# ATTiny85_5LED_VUSB.net
KiCad netlist of a schematic drawn in EAGLE
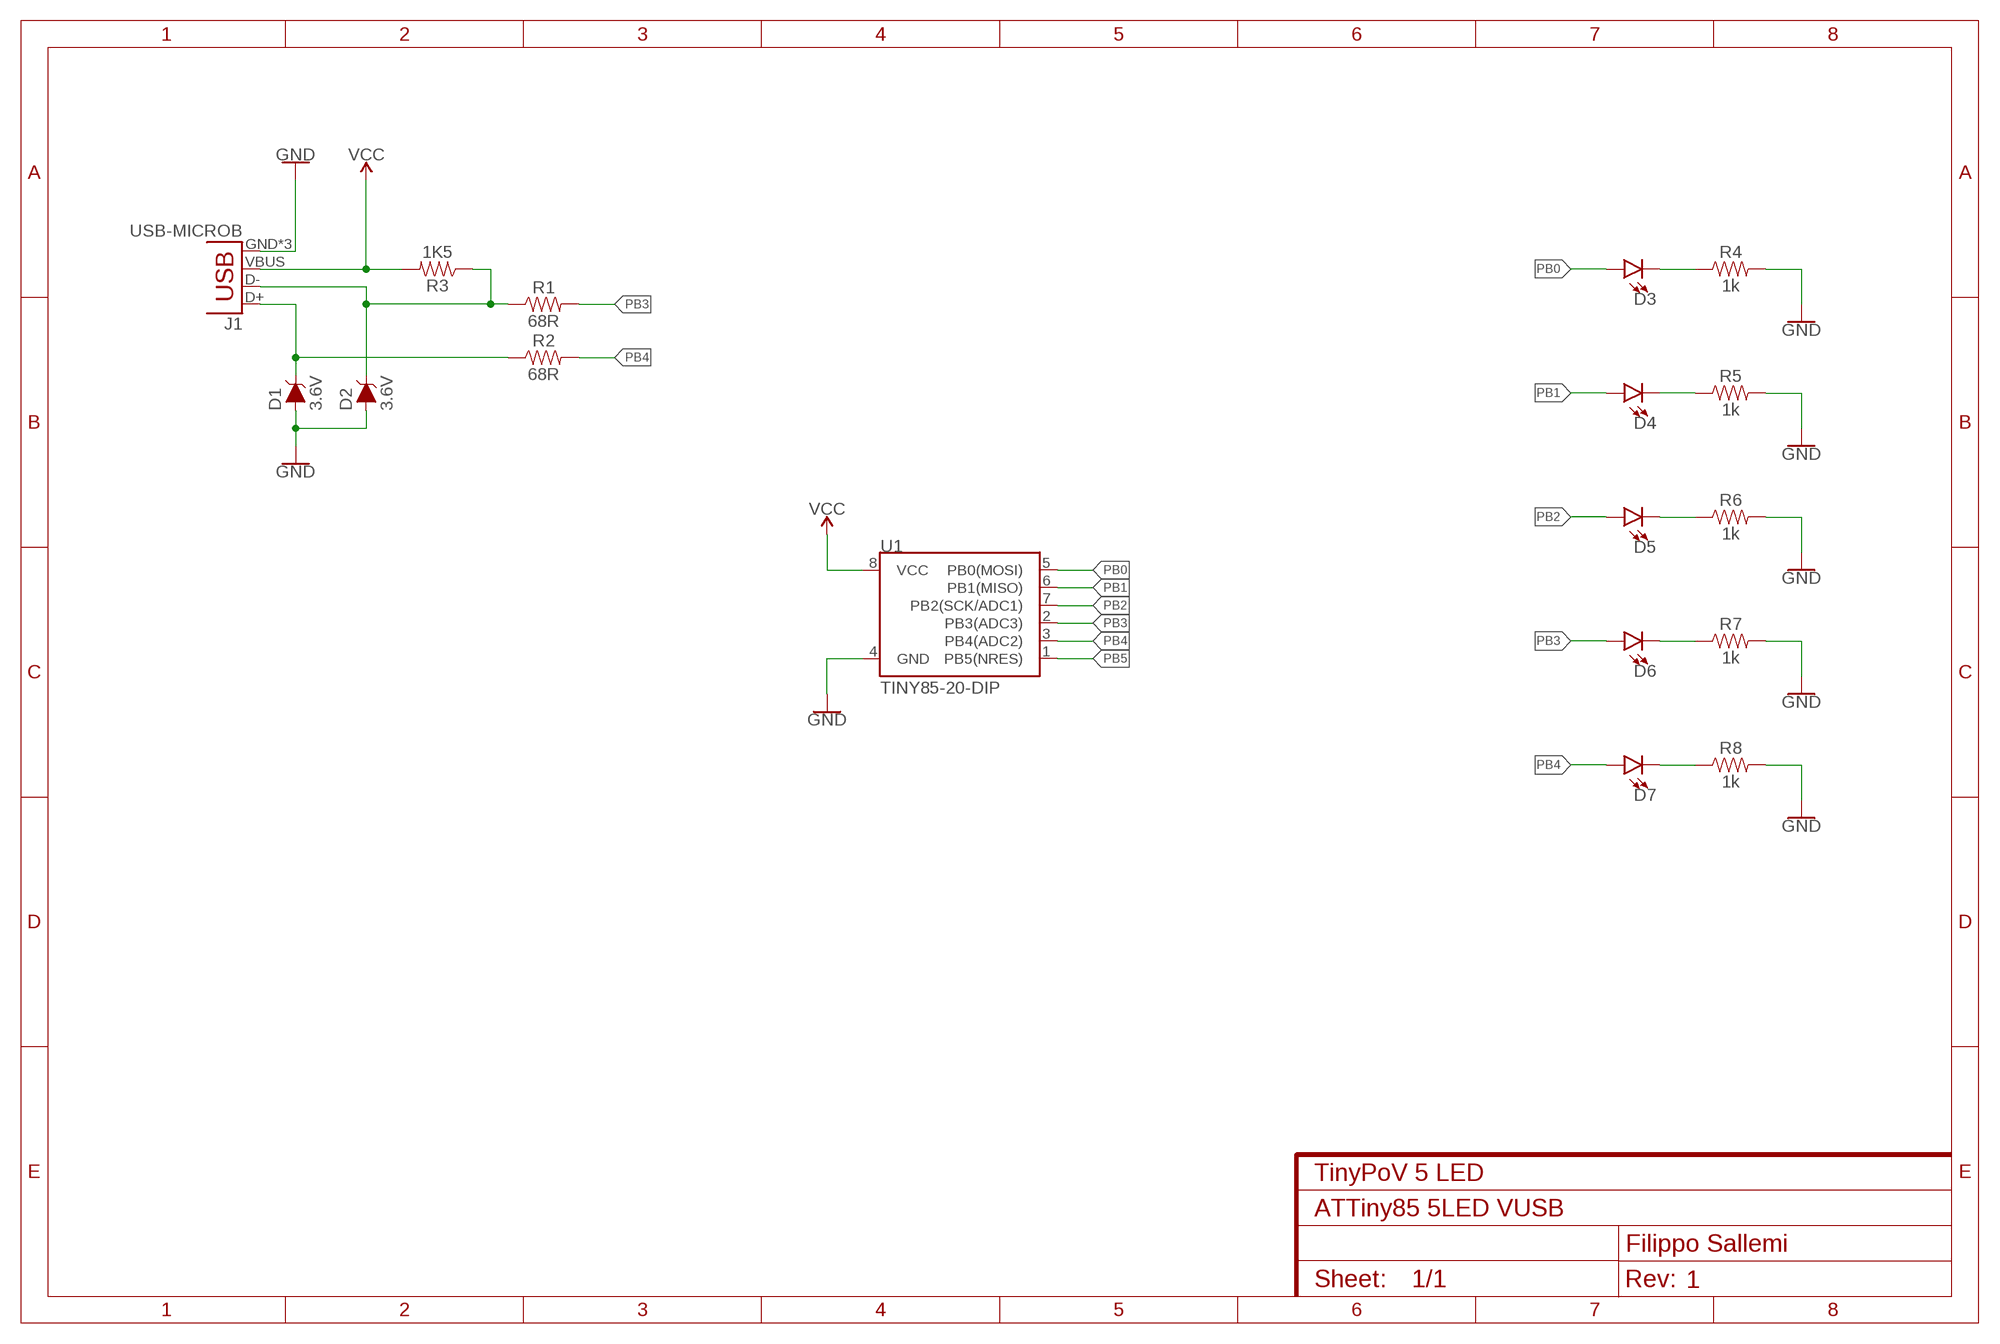
[diagram p0: schematic, sheet 1]

(export (version "E")
  (design (tool "Eeschema 10.0.6"))
  (components
    (comp (ref "D1")
      (value "3.6V")
      (footprint "eagle-import:SOD-323")
      (libsource (lib "eagle-import") (part "DIODE-ZENER-BZT52C3V6S"))
    )
    (comp (ref "D2")
      (value "3.6V")
      (footprint "eagle-import:SOD-323")
      (libsource (lib "eagle-import") (part "DIODE-ZENER-BZT52C3V6S"))
    )
    (comp (ref "D3")
      (value "LED5MM")
      (footprint "eagle-import:LED_5MM")
      (libsource (lib "eagle-import") (part "LED5MM"))
    )
    (comp (ref "D4")
      (value "LED5MM")
      (footprint "eagle-import:LED_5MM")
      (libsource (lib "eagle-import") (part "LED5MM"))
    )
    (comp (ref "D5")
      (value "LED5MM")
      (footprint "eagle-import:LED_5MM")
      (libsource (lib "eagle-import") (part "LED5MM"))
    )
    (comp (ref "D6")
      (value "LED5MM")
      (footprint "eagle-import:LED_5MM")
      (libsource (lib "eagle-import") (part "LED5MM"))
    )
    (comp (ref "D7")
      (value "LED5MM")
      (footprint "eagle-import:LED_5MM")
      (libsource (lib "eagle-import") (part "LED5MM"))
    )
    (comp (ref "J1")
      (value "USB-MICROB")
      (footprint "eagle-import:USB-MICROB")
      (libsource (lib "eagle-import") (part "USB-MICROB"))
    )
    (comp (ref "R1")
      (value "68R")
      (footprint "eagle-import:AXIAL-0.3")
      (libsource (lib "eagle-import") (part "RESISTORAXIAL-0.3"))
    )
    (comp (ref "R2")
      (value "68R")
      (footprint "eagle-import:AXIAL-0.3")
      (libsource (lib "eagle-import") (part "RESISTORAXIAL-0.3"))
    )
    (comp (ref "R3")
      (value "1K5")
      (footprint "eagle-import:AXIAL-0.3")
      (libsource (lib "eagle-import") (part "RESISTORAXIAL-0.3"))
    )
    (comp (ref "R4")
      (value "1k")
      (footprint "eagle-import:AXIAL-0.3")
      (libsource (lib "eagle-import") (part "1KOHM-HORIZ-1/4W-5%"))
    )
    (comp (ref "R5")
      (value "1k")
      (footprint "eagle-import:AXIAL-0.3")
      (libsource (lib "eagle-import") (part "1KOHM-HORIZ-1/4W-5%"))
    )
    (comp (ref "R6")
      (value "1k")
      (footprint "eagle-import:AXIAL-0.3")
      (libsource (lib "eagle-import") (part "1KOHM-HORIZ-1/4W-5%"))
    )
    (comp (ref "R7")
      (value "1k")
      (footprint "eagle-import:AXIAL-0.3")
      (libsource (lib "eagle-import") (part "1KOHM-HORIZ-1/4W-5%"))
    )
    (comp (ref "R8")
      (value "1k")
      (footprint "eagle-import:AXIAL-0.3")
      (libsource (lib "eagle-import") (part "1KOHM-HORIZ-1/4W-5%"))
    )
    (comp (ref "U1")
      (value "TINY85-20-DIP")
      (footprint "eagle-import:DIP08_MCU")
      (libsource (lib "eagle-import") (part "ATTINY45TINY85-20-DIP"))
    )
  )
  (nets
    (net (code "1") (name "GND") (class "Default")
      (node (ref "D1") (pin "A") (pinfunction "A_A") (pintype "passive"))
      (node (ref "D2") (pin "A") (pinfunction "A_A") (pintype "passive"))
      (node (ref "J1") (pin "GND") (pinfunction "GND_GND") (pintype "bidirectional"))
      (node (ref "J1") (pin "MT1") (pinfunction "GND_MT1") (pintype "bidirectional"))
      (node (ref "J1") (pin "MT2") (pinfunction "GND_MT2") (pintype "bidirectional"))
      (node (ref "R4") (pin "P$2") (pinfunction "2_P$2") (pintype "passive"))
      (node (ref "R5") (pin "P$2") (pinfunction "2_P$2") (pintype "passive"))
      (node (ref "R6") (pin "P$2") (pinfunction "2_P$2") (pintype "passive"))
      (node (ref "R7") (pin "P$2") (pinfunction "2_P$2") (pintype "passive"))
      (node (ref "R8") (pin "P$2") (pinfunction "2_P$2") (pintype "passive"))
      (node (ref "U1") (pin "4") (pinfunction "GND_4") (pintype "bidirectional"))
    )
    (net (code "2") (name "Net-(D3-C)") (class "Default")
      (node (ref "D3") (pin "K") (pinfunction "C_K") (pintype "passive"))
      (node (ref "R4") (pin "P$1") (pinfunction "1_P$1") (pintype "passive"))
    )
    (net (code "3") (name "Net-(D4-C)") (class "Default")
      (node (ref "D4") (pin "K") (pinfunction "C_K") (pintype "passive"))
      (node (ref "R5") (pin "P$1") (pinfunction "1_P$1") (pintype "passive"))
    )
    (net (code "4") (name "Net-(D5-C)") (class "Default")
      (node (ref "D5") (pin "K") (pinfunction "C_K") (pintype "passive"))
      (node (ref "R6") (pin "P$1") (pinfunction "1_P$1") (pintype "passive"))
    )
    (net (code "5") (name "Net-(D6-C)") (class "Default")
      (node (ref "D6") (pin "K") (pinfunction "C_K") (pintype "passive"))
      (node (ref "R7") (pin "P$1") (pinfunction "1_P$1") (pintype "passive"))
    )
    (net (code "6") (name "Net-(D7-C)") (class "Default")
      (node (ref "D7") (pin "K") (pinfunction "C_K") (pintype "passive"))
      (node (ref "R8") (pin "P$1") (pinfunction "1_P$1") (pintype "passive"))
    )
    (net (code "7") (name "Net-(R1-1)") (class "Default")
      (node (ref "D2") (pin "C") (pinfunction "C_C") (pintype "passive"))
      (node (ref "J1") (pin "D-") (pinfunction "D-_D-") (pintype "bidirectional"))
      (node (ref "R1") (pin "P$1") (pinfunction "1_P$1") (pintype "passive"))
      (node (ref "R3") (pin "P$1") (pinfunction "1_P$1") (pintype "passive"))
    )
    (net (code "8") (name "Net-(R2-1)") (class "Default")
      (node (ref "D1") (pin "C") (pinfunction "C_C") (pintype "passive"))
      (node (ref "J1") (pin "D+") (pinfunction "D+_D+") (pintype "bidirectional"))
      (node (ref "R2") (pin "P$1") (pinfunction "1_P$1") (pintype "passive"))
    )
    (net (code "9") (name "PB0") (class "Default")
      (node (ref "D3") (pin "A") (pinfunction "A_A") (pintype "passive"))
      (node (ref "U1") (pin "5") (pinfunction "PB0(MOSI)_5") (pintype "bidirectional"))
    )
    (net (code "10") (name "PB1") (class "Default")
      (node (ref "D4") (pin "A") (pinfunction "A_A") (pintype "passive"))
      (node (ref "U1") (pin "6") (pinfunction "PB1(MISO)_6") (pintype "bidirectional"))
    )
    (net (code "11") (name "PB2") (class "Default")
      (node (ref "D5") (pin "A") (pinfunction "A_A") (pintype "passive"))
      (node (ref "U1") (pin "7") (pinfunction "PB2(SCK/ADC1)_7") (pintype "bidirectional"))
    )
    (net (code "12") (name "PB3") (class "Default")
      (node (ref "D6") (pin "A") (pinfunction "A_A") (pintype "passive"))
      (node (ref "R1") (pin "P$2") (pinfunction "2_P$2") (pintype "passive"))
      (node (ref "U1") (pin "2") (pinfunction "PB3(ADC3)_2") (pintype "bidirectional"))
    )
    (net (code "13") (name "PB4") (class "Default")
      (node (ref "D7") (pin "A") (pinfunction "A_A") (pintype "passive"))
      (node (ref "R2") (pin "P$2") (pinfunction "2_P$2") (pintype "passive"))
      (node (ref "U1") (pin "3") (pinfunction "PB4(ADC2)_3") (pintype "bidirectional"))
    )
    (net (code "14") (name "PB5") (class "Default")
      (node (ref "U1") (pin "1") (pinfunction "PB5(NRES)_1") (pintype "bidirectional"))
    )
    (net (code "15") (name "VCC") (class "Default")
      (node (ref "J1") (pin "VBUS") (pinfunction "VBUS_VBUS") (pintype "bidirectional"))
      (node (ref "R3") (pin "P$2") (pinfunction "2_P$2") (pintype "passive"))
      (node (ref "U1") (pin "8") (pinfunction "VCC_8") (pintype "bidirectional"))
    )
  )
)
